# EORE_Connector_and_Filtering.net
KiCad netlist of a schematic drawn in Altium Designer
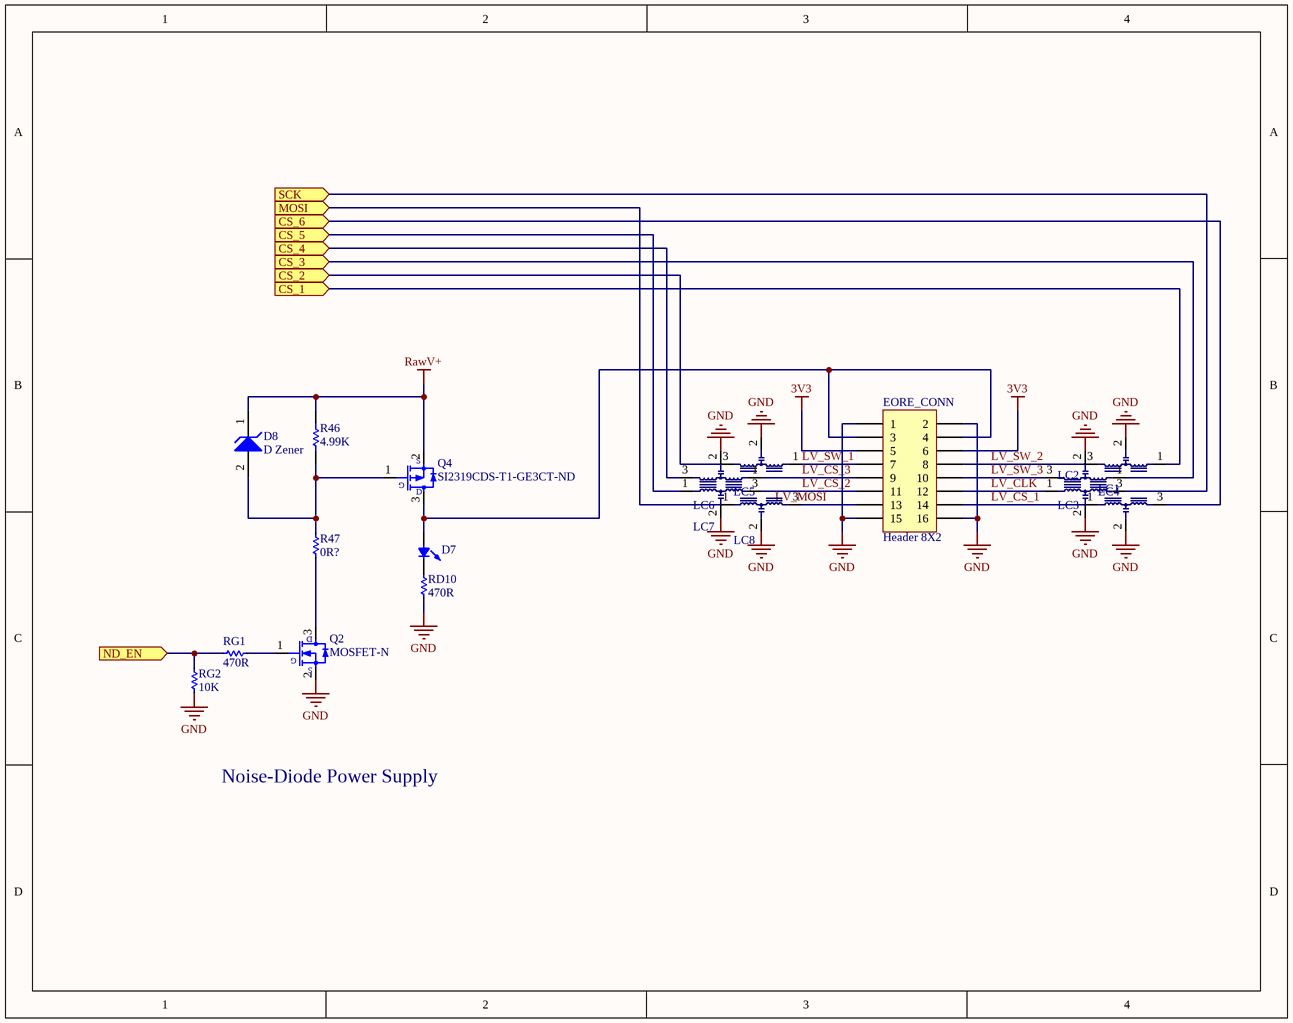
[diagram p0: EORE Connector and Filtering.SchDoc]

(export (version "E")
  (design (tool "Eeschema 10.0.6"))
  (components
    (comp (ref "D7")
      (value "LED0")
      (footprint "0603 SMT LED")
      (description "T 1 3/4 LED")
      (fields (field (name "PUBLISHER") "Altium Limited"))
      (libsource (lib "Miscellaneous Devices") (part "LED0"))
    )
    (comp (ref "D8")
      (value "D Zener")
      (footprint "SOD123/X.85")
      (description "Zener Diode")
      (fields (field (name "PUBLISHER") "Altium Limited"))
      (libsource (lib "Miscellaneous Devices") (part "D Zener"))
    )
    (comp (ref "EORE_CONN")
      (value "Header 8X2")
      (footprint "SMT 16-pin rectangular header")
      (description "Header, 8-Pin, Dual row")
      (fields (field (name "PUBLISHER") "Altium Limited"))
      (libsource (lib "Miscellaneous Connectors") (part "Header 8X2"))
    )
    (comp (ref "LC1")
      (value "MEM2012F")
      (footprint "MEM2012S LC Filter")
      (description "Signal Line 3-terminal Filters")
      (libsource (lib "Unsorted") (part "MEM2012F - Signal Filter"))
    )
    (comp (ref "LC2")
      (value "MEM2012F")
      (footprint "MEM2012S LC Filter")
      (description "Signal Line 3-terminal Filters")
      (libsource (lib "Unsorted") (part "MEM2012F - Signal Filter"))
    )
    (comp (ref "LC3")
      (value "MEM2012F")
      (footprint "MEM2012S LC Filter")
      (description "Signal Line 3-terminal Filters")
      (libsource (lib "Unsorted") (part "MEM2012F - Signal Filter"))
    )
    (comp (ref "LC4")
      (value "MEM2012F")
      (footprint "MEM2012S LC Filter")
      (description "Signal Line 3-terminal Filters")
      (libsource (lib "Unsorted") (part "MEM2012F - Signal Filter"))
    )
    (comp (ref "LC5")
      (value "MEM2012F")
      (footprint "MEM2012S LC Filter")
      (description "Signal Line 3-terminal Filters")
      (libsource (lib "Unsorted") (part "MEM2012F - Signal Filter"))
    )
    (comp (ref "LC6")
      (value "MEM2012F")
      (footprint "MEM2012S LC Filter")
      (description "Signal Line 3-terminal Filters")
      (libsource (lib "Unsorted") (part "MEM2012F - Signal Filter"))
    )
    (comp (ref "LC7")
      (value "MEM2012F")
      (footprint "MEM2012S LC Filter")
      (description "Signal Line 3-terminal Filters")
      (libsource (lib "Unsorted") (part "MEM2012F - Signal Filter"))
    )
    (comp (ref "LC8")
      (value "MEM2012F")
      (footprint "MEM2012S LC Filter")
      (description "Signal Line 3-terminal Filters")
      (libsource (lib "Unsorted") (part "MEM2012F - Signal Filter"))
    )
    (comp (ref "Q2")
      (value "MOSFET-N")
      (footprint "SOT23-3N")
      (description "N-Channel MOSFET")
      (fields (field (name "PUBLISHER") "Altium Limited"))
      (libsource (lib "Miscellaneous Devices") (part "MOSFET-N"))
    )
    (comp (ref "Q4")
      (value "SI2319CDS-T1-GE3CT-ND")
      (footprint "SOT23-3N")
      (description "P-Channel MOSFET")
      (fields (field (name "PUBLISHER") "Altium Limited"))
      (libsource (lib "Miscellaneous Devices") (part "MOSFET-P"))
    )
    (comp (ref "R46")
      (value "4.99K")
      (footprint "0603R")
      (description "Semiconductor Resistor")
      (fields (field (name "Comment") "Res Semi") (field (name "PUBLISHER") "Altium Limited"))
      (libsource (lib "Miscellaneous Devices") (part "Res Semi"))
    )
    (comp (ref "R47")
      (value "0R?")
      (footprint "0603R")
      (description "Semiconductor Resistor")
      (fields (field (name "Comment") "Res Semi Small") (field (name "PUBLISHER") "Altium Limited"))
      (libsource (lib "Miscellaneous Devices") (part "Res Semi Small"))
    )
    (comp (ref "RD10")
      (value "470R")
      (footprint "0603R")
      (description "Semiconductor Resistor")
      (fields (field (name "Comment") "Res Semi Small") (field (name "PUBLISHER") "Altium Limited"))
      (libsource (lib "Miscellaneous Devices") (part "Res Semi Small"))
    )
    (comp (ref "RG1")
      (value "470R")
      (footprint "0603R")
      (description "Semiconductor Resistor")
      (fields (field (name "Comment") "Res Semi Small") (field (name "PUBLISHER") "Altium Limited"))
      (libsource (lib "Miscellaneous Devices") (part "Res Semi Small"))
    )
    (comp (ref "RG2")
      (value "10K")
      (footprint "0603R")
      (description "Semiconductor Resistor")
      (fields (field (name "Comment") "Res Semi Small") (field (name "PUBLISHER") "Altium Limited"))
      (libsource (lib "Miscellaneous Devices") (part "Res Semi Small"))
    )
  )
  (nets
    (net (code "1") (name "/CS_1") (class "Default")
      (node (ref "LC4") (pin "1") (pinfunction "1_1") (pintype "passive"))
    )
    (net (code "2") (name "/CS_2") (class "Default")
      (node (ref "LC5") (pin "3") (pinfunction "3_3") (pintype "passive"))
    )
    (net (code "3") (name "/CS_3") (class "Default")
      (node (ref "LC3") (pin "1") (pinfunction "1_1") (pintype "passive"))
    )
    (net (code "4") (name "/CS_4") (class "Default")
      (node (ref "LC6") (pin "3") (pinfunction "3_3") (pintype "passive"))
    )
    (net (code "5") (name "/CS_5") (class "Default")
      (node (ref "LC7") (pin "1") (pinfunction "1_1") (pintype "passive"))
    )
    (net (code "6") (name "/CS_6") (class "Default")
      (node (ref "LC1") (pin "3") (pinfunction "3_3") (pintype "passive"))
    )
    (net (code "7") (name "/LV_CLK") (class "Default")
      (node (ref "EORE_CONN") (pin "12") (pinfunction "12_12") (pintype "passive"))
      (node (ref "LC2") (pin "1") (pinfunction "1_1") (pintype "passive"))
    )
    (net (code "8") (name "/LV_CS_1") (class "Default")
      (node (ref "EORE_CONN") (pin "14") (pinfunction "14_14") (pintype "passive"))
      (node (ref "LC1") (pin "1") (pinfunction "1_1") (pintype "passive"))
    )
    (net (code "9") (name "/LV_CS_2") (class "Default")
      (node (ref "EORE_CONN") (pin "11") (pinfunction "11_11") (pintype "passive"))
      (node (ref "LC7") (pin "3") (pinfunction "3_3") (pintype "passive"))
    )
    (net (code "10") (name "/LV_CS_3") (class "Default")
      (node (ref "EORE_CONN") (pin "9") (pinfunction "9_9") (pintype "passive"))
      (node (ref "LC6") (pin "1") (pinfunction "1_1") (pintype "passive"))
    )
    (net (code "12") (name "/LV_SW_1") (class "Default")
      (node (ref "EORE_CONN") (pin "7") (pinfunction "7_7") (pintype "passive"))
      (node (ref "LC5") (pin "1") (pinfunction "1_1") (pintype "passive"))
    )
    (net (code "13") (name "/LV_SW_2") (class "Default")
      (node (ref "EORE_CONN") (pin "8") (pinfunction "8_8") (pintype "passive"))
      (node (ref "LC4") (pin "3") (pinfunction "3_3") (pintype "passive"))
    )
    (net (code "14") (name "/LV_SW_3") (class "Default")
      (node (ref "EORE_CONN") (pin "10") (pinfunction "10_10") (pintype "passive"))
      (node (ref "LC3") (pin "3") (pinfunction "3_3") (pintype "passive"))
    )
    (net (code "15") (name "/MOSI") (class "Default")
      (node (ref "LC8") (pin "1") (pinfunction "1_1") (pintype "passive"))
    )
    (net (code "16") (name "/ND_EN") (class "Default")
      (node (ref "RG1") (pin "1") (pinfunction "1_1") (pintype "passive"))
      (node (ref "RG2") (pin "2") (pinfunction "2_2") (pintype "passive"))
    )
    (net (code "17") (name "/SCK") (class "Default")
      (node (ref "LC2") (pin "3") (pinfunction "3_3") (pintype "passive"))
    )
    (net (code "18") (name "3V3") (class "Default")
      (node (ref "EORE_CONN") (pin "5") (pinfunction "5_5") (pintype "passive"))
      (node (ref "EORE_CONN") (pin "6") (pinfunction "6_6") (pintype "passive"))
    )
    (net (code "19") (name "GND") (class "Default")
      (node (ref "EORE_CONN") (pin "1") (pinfunction "1_1") (pintype "passive"))
      (node (ref "EORE_CONN") (pin "15") (pinfunction "15_15") (pintype "passive"))
      (node (ref "EORE_CONN") (pin "16") (pinfunction "16_16") (pintype "passive"))
      (node (ref "EORE_CONN") (pin "2") (pinfunction "2_2") (pintype "passive"))
      (node (ref "LC1") (pin "2") (pinfunction "2_2") (pintype "passive"))
      (node (ref "LC2") (pin "2") (pinfunction "2_2") (pintype "passive"))
      (node (ref "LC3") (pin "2") (pinfunction "2_2") (pintype "passive"))
      (node (ref "LC4") (pin "2") (pinfunction "2_2") (pintype "passive"))
      (node (ref "LC5") (pin "2") (pinfunction "2_2") (pintype "passive"))
      (node (ref "LC6") (pin "2") (pinfunction "2_2") (pintype "passive"))
      (node (ref "LC7") (pin "2") (pinfunction "2_2") (pintype "passive"))
      (node (ref "LC8") (pin "2") (pinfunction "2_2") (pintype "passive"))
      (node (ref "Q2") (pin "2") (pinfunction "S_2") (pintype "passive"))
      (node (ref "RD10") (pin "2") (pinfunction "2_2") (pintype "passive"))
      (node (ref "RG2") (pin "1") (pinfunction "1_1") (pintype "passive"))
    )
    (net (code "20") (name "Net-(D7-Pad2)") (class "Default")
      (node (ref "D7") (pin "2") (pinfunction "2_2") (pintype "passive"))
      (node (ref "RD10") (pin "1") (pinfunction "1_1") (pintype "passive"))
    )
    (net (code "21") (name "Net-(D8-K)") (class "Default")
      (node (ref "D8") (pin "2") (pinfunction "K_2") (pintype "passive"))
      (node (ref "Q4") (pin "1") (pinfunction "G_1") (pintype "passive"))
      (node (ref "R46") (pin "1") (pinfunction "1_1") (pintype "passive"))
      (node (ref "R47") (pin "1") (pinfunction "1_1") (pintype "passive"))
    )
    (net (code "22") (name "Net-(EORE_CONN-Pad13)") (class "Default")
      (node (ref "EORE_CONN") (pin "13") (pinfunction "13_13") (pintype "passive"))
      (node (ref "LC8") (pin "3") (pinfunction "3_3") (pintype "passive"))
    )
    (net (code "23") (name "Net-(Q2-D)") (class "Default")
      (node (ref "Q2") (pin "3") (pinfunction "D_3") (pintype "passive"))
      (node (ref "R47") (pin "2") (pinfunction "2_2") (pintype "passive"))
    )
    (net (code "24") (name "Net-(Q2-G)") (class "Default")
      (node (ref "Q2") (pin "1") (pinfunction "G_1") (pintype "passive"))
      (node (ref "RG1") (pin "2") (pinfunction "2_2") (pintype "passive"))
    )
    (net (code "25") (name "Net-(Q4-S)") (class "Default")
      (node (ref "D7") (pin "1") (pinfunction "1_1") (pintype "passive"))
      (node (ref "EORE_CONN") (pin "3") (pinfunction "3_3") (pintype "passive"))
      (node (ref "EORE_CONN") (pin "4") (pinfunction "4_4") (pintype "passive"))
      (node (ref "Q4") (pin "3") (pinfunction "S_3") (pintype "passive"))
    )
    (net (code "26") (name "RawV+") (class "Default")
      (node (ref "D8") (pin "1") (pinfunction "A_1") (pintype "passive"))
      (node (ref "Q4") (pin "2") (pinfunction "D_2") (pintype "passive"))
      (node (ref "R46") (pin "2") (pinfunction "2_2") (pintype "passive"))
    )
  )
)
